# rpilink222.net
KiCad netlist of a schematic drawn in EAGLE
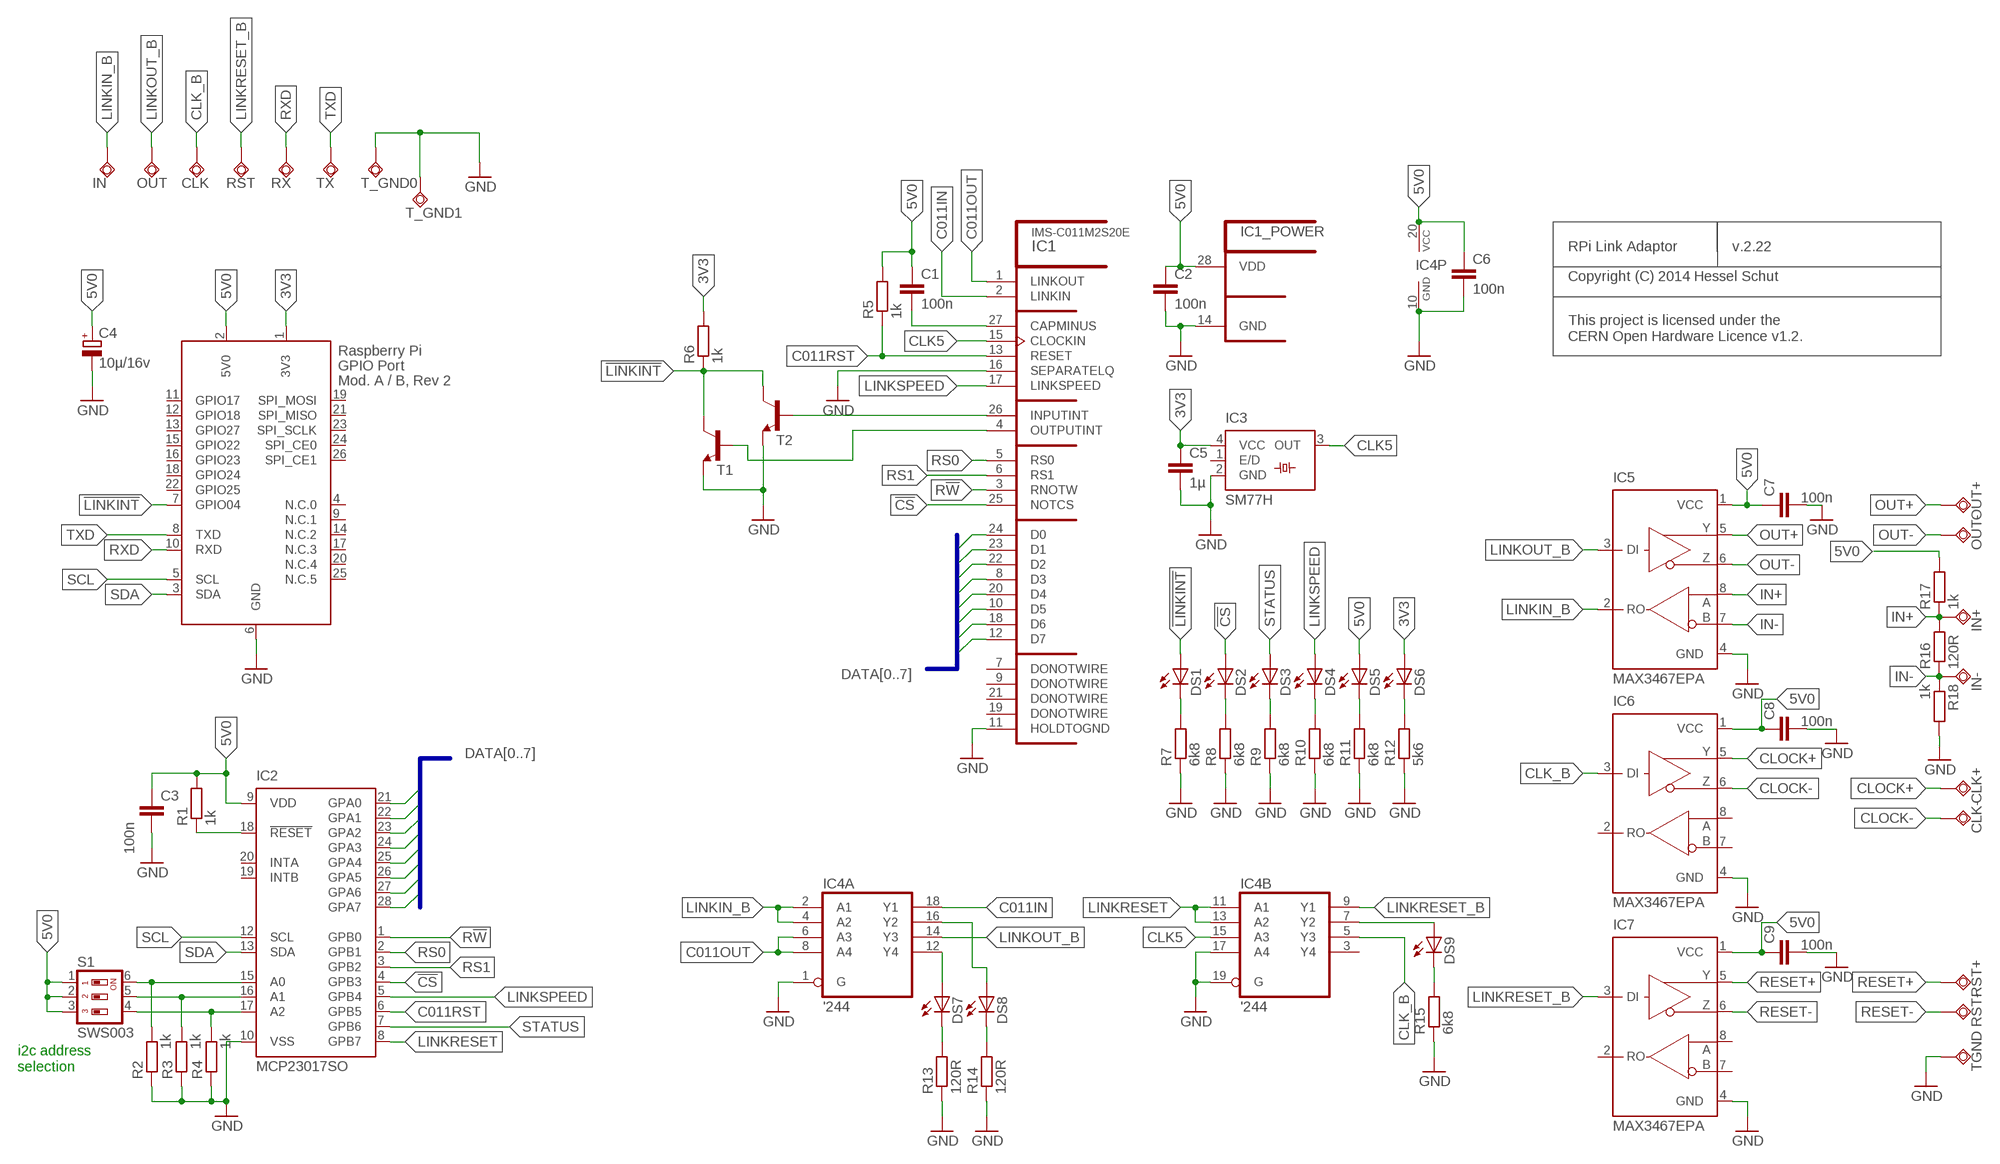
[diagram p0: schematic, sheet 1]

(export (version "E")
  (design (tool "Eeschema 10.0.6"))
  (components
    (comp (ref "C1")
      (value "100n")
      (footprint "eagle-import:C0805")
      (libsource (lib "eagle-import") (part "C-EUC0805"))
    )
    (comp (ref "C2")
      (value "100n")
      (footprint "eagle-import:C0805")
      (libsource (lib "eagle-import") (part "C-EUC0805"))
    )
    (comp (ref "C3")
      (value "100n")
      (footprint "eagle-import:C0805")
      (libsource (lib "eagle-import") (part "C-EUC0805"))
    )
    (comp (ref "C4")
      (value "10µ/16v")
      (footprint "eagle-import:C_6032-28R")
      (libsource (lib "eagle-import") (part "CPOL-EUC/6032-28R"))
    )
    (comp (ref "C5")
      (value "1µ")
      (footprint "eagle-import:C0805")
      (libsource (lib "eagle-import") (part "C-EUC0805"))
    )
    (comp (ref "C6")
      (value "100n")
      (footprint "eagle-import:C0805")
      (libsource (lib "eagle-import") (part "C-EUC0805"))
    )
    (comp (ref "C7")
      (value "100n")
      (footprint "eagle-import:C0805")
      (libsource (lib "eagle-import") (part "C-EUC0805"))
    )
    (comp (ref "C8")
      (value "100n")
      (footprint "eagle-import:C0805")
      (libsource (lib "eagle-import") (part "C-EUC0805"))
    )
    (comp (ref "C9")
      (value "100n")
      (footprint "eagle-import:C0805")
      (libsource (lib "eagle-import") (part "C-EUC0805"))
    )
    (comp (ref "CLK")
      (value "TPSQTP20SQ")
      (footprint "eagle-import:TP20SQ")
      (libsource (lib "eagle-import") (part "TPSQTP20SQ"))
    )
    (comp (ref "CLK+")
      (value "TPSQTP20SQ")
      (footprint "eagle-import:TP20SQ")
      (libsource (lib "eagle-import") (part "TPSQTP20SQ"))
    )
    (comp (ref "CLK-")
      (value "TPSQTP20SQ")
      (footprint "eagle-import:TP20SQ")
      (libsource (lib "eagle-import") (part "TPSQTP20SQ"))
    )
    (comp (ref "DS1")
      (value "LEDCHIP-LED0603")
      (footprint "eagle-import:CHIP-LED0603")
      (libsource (lib "eagle-import") (part "LEDCHIP-LED0603"))
    )
    (comp (ref "DS2")
      (value "LEDCHIP-LED0603")
      (footprint "eagle-import:CHIP-LED0603")
      (libsource (lib "eagle-import") (part "LEDCHIP-LED0603"))
    )
    (comp (ref "DS3")
      (value "LEDCHIP-LED0603")
      (footprint "eagle-import:CHIP-LED0603")
      (libsource (lib "eagle-import") (part "LEDCHIP-LED0603"))
    )
    (comp (ref "DS4")
      (value "LEDCHIP-LED0603")
      (footprint "eagle-import:CHIP-LED0603")
      (libsource (lib "eagle-import") (part "LEDCHIP-LED0603"))
    )
    (comp (ref "DS5")
      (value "LEDCHIP-LED0603")
      (footprint "eagle-import:CHIP-LED0603")
      (libsource (lib "eagle-import") (part "LEDCHIP-LED0603"))
    )
    (comp (ref "DS6")
      (value "LEDCHIP-LED0603")
      (footprint "eagle-import:CHIP-LED0603")
      (libsource (lib "eagle-import") (part "LEDCHIP-LED0603"))
    )
    (comp (ref "DS7")
      (value "LEDCHIP-LED0603")
      (footprint "eagle-import:CHIP-LED0603")
      (libsource (lib "eagle-import") (part "LEDCHIP-LED0603"))
    )
    (comp (ref "DS8")
      (value "LEDCHIP-LED0603")
      (footprint "eagle-import:CHIP-LED0603")
      (libsource (lib "eagle-import") (part "LEDCHIP-LED0603"))
    )
    (comp (ref "DS9")
      (value "LEDCHIP-LED0603")
      (footprint "eagle-import:CHIP-LED0603")
      (libsource (lib "eagle-import") (part "LEDCHIP-LED0603"))
    )
    (comp (ref "IC1")
      (value "IMS-C011M2S20E")
      (footprint "eagle-import:SOJ28-3")
      (libsource (lib "eagle-import") (part "IMS-C011M2ES20"))
    )
    (comp (ref "IC2")
      (value "MCP23017SO")
      (footprint "eagle-import:SO28W")
      (fields (field (name "MF") "MICROCHIP") (field (name "MPN") "MCP23017-E/SO"))
      (libsource (lib "eagle-import") (part "MCP23017SO"))
    )
    (comp (ref "IC3")
      (value "SM77H")
      (footprint "eagle-import:SM77H")
      (libsource (lib "eagle-import") (part "SM77H"))
    )
    (comp (ref "IC4")
      (value "'244")
      (footprint "eagle-import:SO20W")
      (libsource (lib "eagle-import") (part "74244DWAC"))
    )
    (comp (ref "IC5")
      (value "MAX3467EPA")
      (footprint "eagle-import:SO08")
      (libsource (lib "eagle-import") (part "MAX3467PAE"))
    )
    (comp (ref "IC6")
      (value "MAX3467EPA")
      (footprint "eagle-import:SO08")
      (libsource (lib "eagle-import") (part "MAX3467PAE"))
    )
    (comp (ref "IC7")
      (value "MAX3467EPA")
      (footprint "eagle-import:SO08")
      (libsource (lib "eagle-import") (part "MAX3467PAE"))
    )
    (comp (ref "IN")
      (value "TPSQTP20SQ")
      (footprint "eagle-import:TP20SQ")
      (libsource (lib "eagle-import") (part "TPSQTP20SQ"))
    )
    (comp (ref "IN+")
      (value "TPSQTP20SQ")
      (footprint "eagle-import:TP20SQ")
      (libsource (lib "eagle-import") (part "TPSQTP20SQ"))
    )
    (comp (ref "IN-")
      (value "TPSQTP20SQ")
      (footprint "eagle-import:TP20SQ")
      (libsource (lib "eagle-import") (part "TPSQTP20SQ"))
    )
    (comp (ref "OUT")
      (value "TPSQTP20SQ")
      (footprint "eagle-import:TP20SQ")
      (libsource (lib "eagle-import") (part "TPSQTP20SQ"))
    )
    (comp (ref "OUT+")
      (value "TPSQTP20SQ")
      (footprint "eagle-import:TP20SQ")
      (libsource (lib "eagle-import") (part "TPSQTP20SQ"))
    )
    (comp (ref "OUT-")
      (value "TPSQTP20SQ")
      (footprint "eagle-import:TP20SQ")
      (libsource (lib "eagle-import") (part "TPSQTP20SQ"))
    )
    (comp (ref "R1")
      (value "1k")
      (footprint "eagle-import:R0603")
      (libsource (lib "eagle-import") (part "R-EU_R0603"))
    )
    (comp (ref "R2")
      (value "1k")
      (footprint "eagle-import:R0603")
      (libsource (lib "eagle-import") (part "R-EU_R0603"))
    )
    (comp (ref "R3")
      (value "1k")
      (footprint "eagle-import:R0603")
      (libsource (lib "eagle-import") (part "R-EU_R0603"))
    )
    (comp (ref "R4")
      (value "1k")
      (footprint "eagle-import:R0603")
      (libsource (lib "eagle-import") (part "R-EU_R0603"))
    )
    (comp (ref "R5")
      (value "1k")
      (footprint "eagle-import:R0603")
      (libsource (lib "eagle-import") (part "R-EU_R0603"))
    )
    (comp (ref "R6")
      (value "1k")
      (footprint "eagle-import:R0603")
      (libsource (lib "eagle-import") (part "R-EU_R0603"))
    )
    (comp (ref "R7")
      (value "6k8")
      (footprint "eagle-import:R0603")
      (libsource (lib "eagle-import") (part "R-EU_R0603"))
    )
    (comp (ref "R8")
      (value "6k8")
      (footprint "eagle-import:R0603")
      (libsource (lib "eagle-import") (part "R-EU_R0603"))
    )
    (comp (ref "R9")
      (value "6k8")
      (footprint "eagle-import:R0603")
      (libsource (lib "eagle-import") (part "R-EU_R0603"))
    )
    (comp (ref "R10")
      (value "6k8")
      (footprint "eagle-import:R0603")
      (libsource (lib "eagle-import") (part "R-EU_R0603"))
    )
    (comp (ref "R11")
      (value "6k8")
      (footprint "eagle-import:R0603")
      (libsource (lib "eagle-import") (part "R-EU_R0603"))
    )
    (comp (ref "R12")
      (value "5k6")
      (footprint "eagle-import:R0603")
      (libsource (lib "eagle-import") (part "R-EU_R0603"))
    )
    (comp (ref "R13")
      (value "120R")
      (footprint "eagle-import:R0603")
      (libsource (lib "eagle-import") (part "R-EU_R0603"))
    )
    (comp (ref "R14")
      (value "120R")
      (footprint "eagle-import:R0603")
      (libsource (lib "eagle-import") (part "R-EU_R0603"))
    )
    (comp (ref "R15")
      (value "6k8")
      (footprint "eagle-import:R0603")
      (libsource (lib "eagle-import") (part "R-EU_R0603"))
    )
    (comp (ref "R16")
      (value "120R")
      (footprint "eagle-import:R0603")
      (libsource (lib "eagle-import") (part "R-EU_R0603"))
    )
    (comp (ref "R17")
      (value "1k")
      (footprint "eagle-import:R0603")
      (libsource (lib "eagle-import") (part "R-EU_R0603"))
    )
    (comp (ref "R18")
      (value "1k")
      (footprint "eagle-import:R0603")
      (libsource (lib "eagle-import") (part "R-EU_R0603"))
    )
    (comp (ref "RST")
      (value "TPSQTP20SQ")
      (footprint "eagle-import:TP20SQ")
      (libsource (lib "eagle-import") (part "TPSQTP20SQ"))
    )
    (comp (ref "RST+")
      (value "TPSQTP20SQ")
      (footprint "eagle-import:TP20SQ")
      (libsource (lib "eagle-import") (part "TPSQTP20SQ"))
    )
    (comp (ref "RST-")
      (value "TPSQTP20SQ")
      (footprint "eagle-import:TP20SQ")
      (libsource (lib "eagle-import") (part "TPSQTP20SQ"))
    )
    (comp (ref "RX")
      (value "TPSQTP20SQ")
      (footprint "eagle-import:TP20SQ")
      (libsource (lib "eagle-import") (part "TPSQTP20SQ"))
    )
    (comp (ref "S1")
      (value "SWS003")
      (footprint "eagle-import:SMS-003")
      (libsource (lib "eagle-import") (part "SWS003"))
    )
    (comp (ref "T1")
      (value "BC808-NPN-SOT23-BEC")
      (footprint "eagle-import:SOT23-BEC")
      (libsource (lib "eagle-import") (part "-NPN-SOT23-BECBC808"))
    )
    (comp (ref "T2")
      (value "BC808-NPN-SOT23-BEC")
      (footprint "eagle-import:SOT23-BEC")
      (libsource (lib "eagle-import") (part "-NPN-SOT23-BECBC808"))
    )
    (comp (ref "TGND")
      (value "TPSQTP20SQ")
      (footprint "eagle-import:TP20SQ")
      (libsource (lib "eagle-import") (part "TPSQTP20SQ"))
    )
    (comp (ref "TX")
      (value "TPSQTP20SQ")
      (footprint "eagle-import:TP20SQ")
      (libsource (lib "eagle-import") (part "TPSQTP20SQ"))
    )
    (comp (ref "T_GND0")
      (value "TPSQTP20SQ")
      (footprint "eagle-import:TP20SQ")
      (libsource (lib "eagle-import") (part "TPSQTP20SQ"))
    )
    (comp (ref "T_GND1")
      (value "TPSQTP20SQ")
      (footprint "eagle-import:TP20SQ")
      (libsource (lib "eagle-import") (part "TPSQTP20SQ"))
    )
    (comp (ref "X1")
      (value "RASPI_BOARD_AB_E2P")
      (footprint "eagle-import:RASPI_BOARD_AB_EDGES_2DRILL_PAD")
      (libsource (lib "eagle-import") (part "RASPI_BOARD_AB_E2P"))
    )
  )
  (nets
    (net (code "1") (name "/DATA0") (class "Default")
      (node (ref "IC1") (pin "24") (pinfunction "D0_24") (pintype "bidirectional"))
      (node (ref "IC2") (pin "21") (pinfunction "GPA0_21") (pintype "bidirectional"))
    )
    (net (code "2") (name "/DATA1") (class "Default")
      (node (ref "IC1") (pin "23") (pinfunction "D1_23") (pintype "bidirectional"))
      (node (ref "IC2") (pin "22") (pinfunction "GPA1_22") (pintype "bidirectional"))
    )
    (net (code "3") (name "/DATA2") (class "Default")
      (node (ref "IC1") (pin "22") (pinfunction "D2_22") (pintype "bidirectional"))
      (node (ref "IC2") (pin "23") (pinfunction "GPA2_23") (pintype "bidirectional"))
    )
    (net (code "4") (name "/DATA3") (class "Default")
      (node (ref "IC1") (pin "8") (pinfunction "D3_8") (pintype "bidirectional"))
      (node (ref "IC2") (pin "24") (pinfunction "GPA3_24") (pintype "bidirectional"))
    )
    (net (code "5") (name "/DATA4") (class "Default")
      (node (ref "IC1") (pin "20") (pinfunction "D4_20") (pintype "bidirectional"))
      (node (ref "IC2") (pin "25") (pinfunction "GPA4_25") (pintype "bidirectional"))
    )
    (net (code "6") (name "/DATA5") (class "Default")
      (node (ref "IC1") (pin "10") (pinfunction "D5_10") (pintype "bidirectional"))
      (node (ref "IC2") (pin "26") (pinfunction "GPA5_26") (pintype "bidirectional"))
    )
    (net (code "7") (name "/DATA6") (class "Default")
      (node (ref "IC1") (pin "18") (pinfunction "D6_18") (pintype "bidirectional"))
      (node (ref "IC2") (pin "27") (pinfunction "GPA6_27") (pintype "bidirectional"))
    )
    (net (code "8") (name "/DATA7") (class "Default")
      (node (ref "IC1") (pin "12") (pinfunction "D7_12") (pintype "bidirectional"))
      (node (ref "IC2") (pin "28") (pinfunction "GPA7_28") (pintype "bidirectional"))
    )
    (net (code "10") (name "/R~{W}") (class "Default")
      (node (ref "IC1") (pin "3") (pinfunction "RNOTW_3") (pintype "input"))
      (node (ref "IC2") (pin "1") (pinfunction "GPB0_1") (pintype "bidirectional"))
    )
    (net (code "11") (name "/~{CS}") (class "Default")
      (node (ref "DS2") (pin "A") (pinfunction "A_A") (pintype "passive"))
      (node (ref "IC1") (pin "25") (pinfunction "NOTCS_25") (pintype "input"))
      (node (ref "IC2") (pin "4") (pinfunction "GPB3_4") (pintype "bidirectional"))
    )
    (net (code "12") (name "/~{LINKINT}") (class "Default")
      (node (ref "DS1") (pin "A") (pinfunction "A_A") (pintype "passive"))
      (node (ref "R6") (pin "1") (pinfunction "1_1") (pintype "passive"))
      (node (ref "T1") (pin "C") (pinfunction "C_C") (pintype "passive"))
      (node (ref "T2") (pin "C") (pinfunction "C_C") (pintype "passive"))
      (node (ref "X1") (pin "7") (pinfunction "GPIO04_7") (pintype "bidirectional"))
    )
    (net (code "13") (name "3V3") (class "Default")
      (node (ref "C5") (pin "1") (pinfunction "1_1") (pintype "passive"))
      (node (ref "DS6") (pin "A") (pinfunction "A_A") (pintype "passive"))
      (node (ref "IC3") (pin "4") (pinfunction "VCC_4") (pintype "power_in"))
      (node (ref "R6") (pin "2") (pinfunction "2_2") (pintype "passive"))
      (node (ref "X1") (pin "1") (pinfunction "3V3_1") (pintype "power_in"))
    )
    (net (code "14") (name "5V0") (class "Default")
      (node (ref "C1") (pin "1") (pinfunction "1_1") (pintype "passive"))
      (node (ref "C2") (pin "1") (pinfunction "1_1") (pintype "passive"))
      (node (ref "C3") (pin "1") (pinfunction "1_1") (pintype "passive"))
      (node (ref "C4") (pin "+") (pinfunction "+_+") (pintype "passive"))
      (node (ref "C6") (pin "1") (pinfunction "1_1") (pintype "passive"))
      (node (ref "C7") (pin "1") (pinfunction "1_1") (pintype "passive"))
      (node (ref "C8") (pin "1") (pinfunction "1_1") (pintype "passive"))
      (node (ref "C9") (pin "1") (pinfunction "1_1") (pintype "passive"))
      (node (ref "DS5") (pin "A") (pinfunction "A_A") (pintype "passive"))
      (node (ref "IC1") (pin "28") (pinfunction "VDD_28") (pintype "power_in"))
      (node (ref "IC2") (pin "9") (pinfunction "VDD_9") (pintype "power_in"))
      (node (ref "IC4") (pin "20") (pinfunction "VCC_20") (pintype "power_in"))
      (node (ref "IC5") (pin "1") (pinfunction "VCC_1") (pintype "power_in"))
      (node (ref "IC6") (pin "1") (pinfunction "VCC_1") (pintype "power_in"))
      (node (ref "IC7") (pin "1") (pinfunction "VCC_1") (pintype "power_in"))
      (node (ref "R1") (pin "2") (pinfunction "2_2") (pintype "passive"))
      (node (ref "R17") (pin "2") (pinfunction "2_2") (pintype "passive"))
      (node (ref "R5") (pin "2") (pinfunction "2_2") (pintype "passive"))
      (node (ref "S1") (pin "1") (pinfunction "1_1") (pintype "passive"))
      (node (ref "S1") (pin "2") (pinfunction "2_2") (pintype "passive"))
      (node (ref "S1") (pin "3") (pinfunction "3_3") (pintype "passive"))
      (node (ref "X1") (pin "2") (pinfunction "5V0_2") (pintype "power_in"))
    )
    (net (code "15") (name "C011IN") (class "Default")
      (node (ref "IC1") (pin "2") (pinfunction "LINKIN_2") (pintype "input"))
      (node (ref "IC4") (pin "18") (pinfunction "Y1_18") (pintype "tri_state"))
    )
    (net (code "16") (name "C011OUT") (class "Default")
      (node (ref "IC1") (pin "1") (pinfunction "LINKOUT_1") (pintype "output"))
      (node (ref "IC4") (pin "6") (pinfunction "A3_6") (pintype "input"))
      (node (ref "IC4") (pin "8") (pinfunction "A4_8") (pintype "input"))
    )
    (net (code "17") (name "C011RST") (class "Default")
      (node (ref "IC1") (pin "13") (pinfunction "RESET_13") (pintype "input"))
      (node (ref "IC2") (pin "6") (pinfunction "GPB5_6") (pintype "bidirectional"))
      (node (ref "R5") (pin "1") (pinfunction "1_1") (pintype "passive"))
    )
    (net (code "18") (name "CLK5") (class "Default")
      (node (ref "IC1") (pin "15") (pinfunction "CLOCKIN_15") (pintype "input"))
      (node (ref "IC3") (pin "3") (pinfunction "OUT_3") (pintype "output"))
      (node (ref "IC4") (pin "15") (pinfunction "A3_15") (pintype "input"))
    )
    (net (code "19") (name "CLK_B") (class "Default")
      (node (ref "CLK") (pin "TP") (pinfunction "TP_TP") (pintype "input"))
      (node (ref "IC4") (pin "5") (pinfunction "Y3_5") (pintype "tri_state"))
      (node (ref "IC6") (pin "3") (pinfunction "DI_3") (pintype "input"))
    )
    (net (code "20") (name "CLOCK+") (class "Default")
      (node (ref "CLK+") (pin "TP") (pinfunction "TP_TP") (pintype "input"))
      (node (ref "IC6") (pin "5") (pinfunction "Y_5") (pintype "passive"))
    )
    (net (code "21") (name "CLOCK-") (class "Default")
      (node (ref "CLK-") (pin "TP") (pinfunction "TP_TP") (pintype "input"))
      (node (ref "IC6") (pin "6") (pinfunction "Z_6") (pintype "passive"))
    )
    (net (code "22") (name "GND") (class "Default")
      (node (ref "C2") (pin "2") (pinfunction "2_2") (pintype "passive"))
      (node (ref "C3") (pin "2") (pinfunction "2_2") (pintype "passive"))
      (node (ref "C4") (pin "-") (pinfunction "-_-") (pintype "passive"))
      (node (ref "C5") (pin "2") (pinfunction "2_2") (pintype "passive"))
      (node (ref "C6") (pin "2") (pinfunction "2_2") (pintype "passive"))
      (node (ref "C7") (pin "2") (pinfunction "2_2") (pintype "passive"))
      (node (ref "C8") (pin "2") (pinfunction "2_2") (pintype "passive"))
      (node (ref "C9") (pin "2") (pinfunction "2_2") (pintype "passive"))
      (node (ref "IC1") (pin "11") (pinfunction "HOLDTOGND_11") (pintype "passive"))
      (node (ref "IC1") (pin "14") (pinfunction "GND_14") (pintype "power_in"))
      (node (ref "IC1") (pin "16") (pinfunction "SEPARATELQ_16") (pintype "input"))
      (node (ref "IC2") (pin "10") (pinfunction "VSS_10") (pintype "power_in"))
      (node (ref "IC3") (pin "2") (pinfunction "GND_2") (pintype "power_in"))
      (node (ref "IC4") (pin "1") (pinfunction "G_1") (pintype "input"))
      (node (ref "IC4") (pin "10") (pinfunction "GND_10") (pintype "power_in"))
      (node (ref "IC4") (pin "17") (pinfunction "A4_17") (pintype "input"))
      (node (ref "IC4") (pin "19") (pinfunction "G_19") (pintype "input"))
      (node (ref "IC5") (pin "4") (pinfunction "GND_4") (pintype "power_in"))
      (node (ref "IC6") (pin "4") (pinfunction "GND_4") (pintype "power_in"))
      (node (ref "IC7") (pin "4") (pinfunction "GND_4") (pintype "power_in"))
      (node (ref "R10") (pin "1") (pinfunction "1_1") (pintype "passive"))
      (node (ref "R11") (pin "1") (pinfunction "1_1") (pintype "passive"))
      (node (ref "R12") (pin "1") (pinfunction "1_1") (pintype "passive"))
      (node (ref "R13") (pin "1") (pinfunction "1_1") (pintype "passive"))
      (node (ref "R14") (pin "1") (pinfunction "1_1") (pintype "passive"))
      (node (ref "R15") (pin "1") (pinfunction "1_1") (pintype "passive"))
      (node (ref "R18") (pin "2") (pinfunction "2_2") (pintype "passive"))
      (node (ref "R2") (pin "1") (pinfunction "1_1") (pintype "passive"))
      (node (ref "R3") (pin "1") (pinfunction "1_1") (pintype "passive"))
      (node (ref "R4") (pin "1") (pinfunction "1_1") (pintype "passive"))
      (node (ref "R7") (pin "1") (pinfunction "1_1") (pintype "passive"))
      (node (ref "R8") (pin "1") (pinfunction "1_1") (pintype "passive"))
      (node (ref "R9") (pin "1") (pinfunction "1_1") (pintype "passive"))
      (node (ref "T1") (pin "E") (pinfunction "E_E") (pintype "passive"))
      (node (ref "T2") (pin "E") (pinfunction "E_E") (pintype "passive"))
      (node (ref "TGND") (pin "TP") (pinfunction "TP_TP") (pintype "input"))
      (node (ref "T_GND0") (pin "TP") (pinfunction "TP_TP") (pintype "input"))
      (node (ref "T_GND1") (pin "TP") (pinfunction "TP_TP") (pintype "input"))
      (node (ref "X1") (pin "6") (pinfunction "GND_6") (pintype "power_in"))
    )
    (net (code "23") (name "IN+") (class "Default")
      (node (ref "IC5") (pin "8") (pinfunction "A_8") (pintype "passive"))
      (node (ref "IN+") (pin "TP") (pinfunction "TP_TP") (pintype "input"))
      (node (ref "R16") (pin "2") (pinfunction "2_2") (pintype "passive"))
      (node (ref "R17") (pin "1") (pinfunction "1_1") (pintype "passive"))
    )
    (net (code "24") (name "IN-") (class "Default")
      (node (ref "IC5") (pin "7") (pinfunction "B_7") (pintype "passive"))
      (node (ref "IN-") (pin "TP") (pinfunction "TP_TP") (pintype "input"))
      (node (ref "R16") (pin "1") (pinfunction "1_1") (pintype "passive"))
      (node (ref "R18") (pin "1") (pinfunction "1_1") (pintype "passive"))
    )
    (net (code "25") (name "LINKIN_B") (class "Default")
      (node (ref "IC4") (pin "2") (pinfunction "A1_2") (pintype "input"))
      (node (ref "IC4") (pin "4") (pinfunction "A2_4") (pintype "input"))
      (node (ref "IC5") (pin "2") (pinfunction "RO_2") (pintype "output"))
      (node (ref "IN") (pin "TP") (pinfunction "TP_TP") (pintype "input"))
    )
    (net (code "26") (name "LINKOUT_B") (class "Default")
      (node (ref "IC4") (pin "14") (pinfunction "Y3_14") (pintype "tri_state"))
      (node (ref "IC5") (pin "3") (pinfunction "DI_3") (pintype "input"))
      (node (ref "OUT") (pin "TP") (pinfunction "TP_TP") (pintype "input"))
    )
    (net (code "27") (name "LINKRESET") (class "Default")
      (node (ref "IC2") (pin "8") (pinfunction "GPB7_8") (pintype "bidirectional"))
      (node (ref "IC4") (pin "11") (pinfunction "A1_11") (pintype "input"))
      (node (ref "IC4") (pin "13") (pinfunction "A2_13") (pintype "input"))
    )
    (net (code "28") (name "LINKRESET_B") (class "Default")
      (node (ref "IC4") (pin "9") (pinfunction "Y1_9") (pintype "tri_state"))
      (node (ref "IC7") (pin "3") (pinfunction "DI_3") (pintype "input"))
      (node (ref "RST") (pin "TP") (pinfunction "TP_TP") (pintype "input"))
    )
    (net (code "29") (name "LINKSPEED") (class "Default")
      (node (ref "DS4") (pin "A") (pinfunction "A_A") (pintype "passive"))
      (node (ref "IC1") (pin "17") (pinfunction "LINKSPEED_17") (pintype "input"))
      (node (ref "IC2") (pin "5") (pinfunction "GPB4_5") (pintype "bidirectional"))
    )
    (net (code "30") (name "Net-(DS1-PadC)") (class "Default")
      (node (ref "DS1") (pin "C") (pinfunction "C_C") (pintype "passive"))
      (node (ref "R7") (pin "2") (pinfunction "2_2") (pintype "passive"))
    )
    (net (code "31") (name "Net-(DS2-PadC)") (class "Default")
      (node (ref "DS2") (pin "C") (pinfunction "C_C") (pintype "passive"))
      (node (ref "R8") (pin "2") (pinfunction "2_2") (pintype "passive"))
    )
    (net (code "32") (name "Net-(DS3-PadC)") (class "Default")
      (node (ref "DS3") (pin "C") (pinfunction "C_C") (pintype "passive"))
      (node (ref "R9") (pin "2") (pinfunction "2_2") (pintype "passive"))
    )
    (net (code "33") (name "Net-(DS4-PadC)") (class "Default")
      (node (ref "DS4") (pin "C") (pinfunction "C_C") (pintype "passive"))
      (node (ref "R10") (pin "2") (pinfunction "2_2") (pintype "passive"))
    )
    (net (code "34") (name "Net-(DS5-PadC)") (class "Default")
      (node (ref "DS5") (pin "C") (pinfunction "C_C") (pintype "passive"))
      (node (ref "R11") (pin "2") (pinfunction "2_2") (pintype "passive"))
    )
    (net (code "35") (name "Net-(DS6-PadC)") (class "Default")
      (node (ref "DS6") (pin "C") (pinfunction "C_C") (pintype "passive"))
      (node (ref "R12") (pin "2") (pinfunction "2_2") (pintype "passive"))
    )
    (net (code "36") (name "Net-(DS7-PadC)") (class "Default")
      (node (ref "DS7") (pin "C") (pinfunction "C_C") (pintype "passive"))
      (node (ref "R13") (pin "2") (pinfunction "2_2") (pintype "passive"))
    )
    (net (code "37") (name "Net-(DS8-PadC)") (class "Default")
      (node (ref "DS8") (pin "C") (pinfunction "C_C") (pintype "passive"))
      (node (ref "R14") (pin "2") (pinfunction "2_2") (pintype "passive"))
    )
    (net (code "38") (name "Net-(DS9-PadC)") (class "Default")
      (node (ref "DS9") (pin "C") (pinfunction "C_C") (pintype "passive"))
      (node (ref "R15") (pin "2") (pinfunction "2_2") (pintype "passive"))
    )
    (net (code "39") (name "Net-(IC1A-CAPMINUS)") (class "Default")
      (node (ref "C1") (pin "2") (pinfunction "2_2") (pintype "passive"))
      (node (ref "IC1") (pin "27") (pinfunction "CAPMINUS_27") (pintype "passive"))
    )
    (net (code "40") (name "Net-(IC1A-INPUTINT)") (class "Default")
      (node (ref "IC1") (pin "26") (pinfunction "INPUTINT_26") (pintype "output"))
      (node (ref "T2") (pin "B") (pinfunction "B_B") (pintype "passive"))
    )
    (net (code "41") (name "Net-(IC1A-OUTPUTINT)") (class "Default")
      (node (ref "IC1") (pin "4") (pinfunction "OUTPUTINT_4") (pintype "output"))
      (node (ref "T1") (pin "B") (pinfunction "B_B") (pintype "passive"))
    )
    (net (code "42") (name "Net-(IC2-A0)") (class "Default")
      (node (ref "IC2") (pin "15") (pinfunction "A0_15") (pintype "input"))
      (node (ref "R2") (pin "2") (pinfunction "2_2") (pintype "passive"))
      (node (ref "S1") (pin "6") (pinfunction "6_6") (pintype "passive"))
    )
    (net (code "43") (name "Net-(IC2-A1)") (class "Default")
      (node (ref "IC2") (pin "16") (pinfunction "A1_16") (pintype "input"))
      (node (ref "R3") (pin "2") (pinfunction "2_2") (pintype "passive"))
      (node (ref "S1") (pin "5") (pinfunction "5_5") (pintype "passive"))
    )
    (net (code "44") (name "Net-(IC2-A2)") (class "Default")
      (node (ref "IC2") (pin "17") (pinfunction "A2_17") (pintype "input"))
      (node (ref "R4") (pin "2") (pinfunction "2_2") (pintype "passive"))
      (node (ref "S1") (pin "4") (pinfunction "4_4") (pintype "passive"))
    )
    (net (code "45") (name "Net-(IC2-~{RESET})") (class "Default")
      (node (ref "IC2") (pin "18") (pinfunction "~{RESET}_18") (pintype "input"))
      (node (ref "R1") (pin "1") (pinfunction "1_1") (pintype "passive"))
    )
    (net (code "46") (name "Net-(IC4A-Y2)") (class "Default")
      (node (ref "DS8") (pin "A") (pinfunction "A_A") (pintype "passive"))
      (node (ref "IC4") (pin "16") (pinfunction "Y2_16") (pintype "tri_state"))
    )
    (net (code "47") (name "Net-(IC4A-Y4)") (class "Default")
      (node (ref "DS7") (pin "A") (pinfunction "A_A") (pintype "passive"))
      (node (ref "IC4") (pin "12") (pinfunction "Y4_12") (pintype "tri_state"))
    )
    (net (code "48") (name "Net-(IC4B-Y2)") (class "Default")
      (node (ref "DS9") (pin "A") (pinfunction "A_A") (pintype "passive"))
      (node (ref "IC4") (pin "7") (pinfunction "Y2_7") (pintype "tri_state"))
    )
    (net (code "49") (name "OUT+") (class "Default")
      (node (ref "IC5") (pin "5") (pinfunction "Y_5") (pintype "passive"))
      (node (ref "OUT+") (pin "TP") (pinfunction "TP_TP") (pintype "input"))
    )
    (net (code "50") (name "OUT-") (class "Default")
      (node (ref "IC5") (pin "6") (pinfunction "Z_6") (pintype "passive"))
      (node (ref "OUT-") (pin "TP") (pinfunction "TP_TP") (pintype "input"))
    )
    (net (code "51") (name "RESET+") (class "Default")
      (node (ref "IC7") (pin "5") (pinfunction "Y_5") (pintype "passive"))
      (node (ref "RST+") (pin "TP") (pinfunction "TP_TP") (pintype "input"))
    )
    (net (code "52") (name "RESET-") (class "Default")
      (node (ref "IC7") (pin "6") (pinfunction "Z_6") (pintype "passive"))
      (node (ref "RST-") (pin "TP") (pinfunction "TP_TP") (pintype "input"))
    )
    (net (code "53") (name "RS0") (class "Default")
      (node (ref "IC1") (pin "5") (pinfunction "RS0_5") (pintype "input"))
      (node (ref "IC2") (pin "2") (pinfunction "GPB1_2") (pintype "bidirectional"))
    )
    (net (code "54") (name "RS1") (class "Default")
      (node (ref "IC1") (pin "6") (pinfunction "RS1_6") (pintype "input"))
      (node (ref "IC2") (pin "3") (pinfunction "GPB2_3") (pintype "bidirectional"))
    )
    (net (code "55") (name "RXD") (class "Default")
      (node (ref "RX") (pin "TP") (pinfunction "TP_TP") (pintype "input"))
      (node (ref "X1") (pin "10") (pinfunction "RXD_10") (pintype "bidirectional"))
    )
    (net (code "56") (name "SCL") (class "Default")
      (node (ref "IC2") (pin "12") (pinfunction "SCL_12") (pintype "input"))
      (node (ref "X1") (pin "5") (pinfunction "SCL_5") (pintype "bidirectional"))
    )
    (net (code "57") (name "SDA") (class "Default")
      (node (ref "IC2") (pin "13") (pinfunction "SDA_13") (pintype "bidirectional"))
      (node (ref "X1") (pin "3") (pinfunction "SDA_3") (pintype "bidirectional"))
    )
    (net (code "58") (name "STATUS") (class "Default")
      (node (ref "DS3") (pin "A") (pinfunction "A_A") (pintype "passive"))
      (node (ref "IC2") (pin "7") (pinfunction "GPB6_7") (pintype "bidirectional"))
    )
    (net (code "59") (name "TXD") (class "Default")
      (node (ref "TX") (pin "TP") (pinfunction "TP_TP") (pintype "input"))
      (node (ref "X1") (pin "8") (pinfunction "TXD_8") (pintype "bidirectional"))
    )
    (net (code "60") (name "unconnected-(IC1A-DONOTWIRE-Pad7)") (class "Default")
      (node (ref "IC1") (pin "7") (pinfunction "DONOTWIRE_7") (pintype "no_connect"))
    )
    (net (code "61") (name "unconnected-(IC1A-DONOTWIRE-Pad9)") (class "Default")
      (node (ref "IC1") (pin "9") (pinfunction "DONOTWIRE_9") (pintype "no_connect"))
    )
    (net (code "62") (name "unconnected-(IC1A-DONOTWIRE-Pad19)") (class "Default")
      (node (ref "IC1") (pin "19") (pinfunction "DONOTWIRE_19") (pintype "no_connect"))
    )
    (net (code "63") (name "unconnected-(IC1A-DONOTWIRE-Pad21)") (class "Default")
      (node (ref "IC1") (pin "21") (pinfunction "DONOTWIRE_21") (pintype "no_connect"))
    )
    (net (code "64") (name "unconnected-(IC2-INTA-Pad20)") (class "Default")
      (node (ref "IC2") (pin "20") (pinfunction "INTA_20") (pintype "output"))
    )
    (net (code "65") (name "unconnected-(IC2-INTB-Pad19)") (class "Default")
      (node (ref "IC2") (pin "19") (pinfunction "INTB_19") (pintype "output"))
    )
    (net (code "66") (name "unconnected-(IC3-E{slash}D-Pad1)") (class "Default")
      (node (ref "IC3") (pin "1") (pinfunction "E/D_1") (pintype "input"))
    )
    (net (code "67") (name "unconnected-(IC4B-Y4-Pad3)") (class "Default")
      (node (ref "IC4") (pin "3") (pinfunction "Y4_3") (pintype "tri_state"))
    )
    (net (code "68") (name "unconnected-(IC6-A-Pad8)") (class "Default")
      (node (ref "IC6") (pin "8") (pinfunction "A_8") (pintype "passive"))
    )
    (net (code "69") (name "unconnected-(IC6-B-Pad7)") (class "Default")
      (node (ref "IC6") (pin "7") (pinfunction "B_7") (pintype "passive"))
    )
    (net (code "70") (name "unconnected-(IC6-RO-Pad2)") (class "Default")
      (node (ref "IC6") (pin "2") (pinfunction "RO_2") (pintype "output"))
    )
    (net (code "71") (name "unconnected-(IC7-A-Pad8)") (class "Default")
      (node (ref "IC7") (pin "8") (pinfunction "A_8") (pintype "passive"))
    )
    (net (code "72") (name "unconnected-(IC7-B-Pad7)") (class "Default")
      (node (ref "IC7") (pin "7") (pinfunction "B_7") (pintype "passive"))
    )
    (net (code "73") (name "unconnected-(IC7-RO-Pad2)") (class "Default")
      (node (ref "IC7") (pin "2") (pinfunction "RO_2") (pintype "output"))
    )
    (net (code "74") (name "unconnected-(X1-GPIO17-Pad11)") (class "Default")
      (node (ref "X1") (pin "11") (pinfunction "GPIO17_11") (pintype "bidirectional"))
    )
    (net (code "75") (name "unconnected-(X1-GPIO18-Pad12)") (class "Default")
      (node (ref "X1") (pin "12") (pinfunction "GPIO18_12") (pintype "bidirectional"))
    )
    (net (code "76") (name "unconnected-(X1-GPIO22-Pad15)") (class "Default")
      (node (ref "X1") (pin "15") (pinfunction "GPIO22_15") (pintype "bidirectional"))
    )
    (net (code "77") (name "unconnected-(X1-GPIO23-Pad16)") (class "Default")
      (node (ref "X1") (pin "16") (pinfunction "GPIO23_16") (pintype "bidirectional"))
    )
    (net (code "78") (name "unconnected-(X1-GPIO24-Pad18)") (class "Default")
      (node (ref "X1") (pin "18") (pinfunction "GPIO24_18") (pintype "bidirectional"))
    )
    (net (code "79") (name "unconnected-(X1-GPIO25-Pad22)") (class "Default")
      (node (ref "X1") (pin "22") (pinfunction "GPIO25_22") (pintype "bidirectional"))
    )
    (net (code "80") (name "unconnected-(X1-GPIO27-Pad13)") (class "Default")
      (node (ref "X1") (pin "13") (pinfunction "GPIO27_13") (pintype "bidirectional"))
    )
    (net (code "81") (name "unconnected-(X1-N.C.0-Pad4)") (class "Default")
      (node (ref "X1") (pin "4") (pinfunction "N.C.0_4") (pintype "no_connect"))
    )
    (net (code "82") (name "unconnected-(X1-N.C.1-Pad9)") (class "Default")
      (node (ref "X1") (pin "9") (pinfunction "N.C.1_9") (pintype "no_connect"))
    )
    (net (code "83") (name "unconnected-(X1-N.C.2-Pad14)") (class "Default")
      (node (ref "X1") (pin "14") (pinfunction "N.C.2_14") (pintype "no_connect"))
    )
    (net (code "84") (name "unconnected-(X1-N.C.3-Pad17)") (class "Default")
      (node (ref "X1") (pin "17") (pinfunction "N.C.3_17") (pintype "no_connect"))
    )
    (net (code "85") (name "unconnected-(X1-N.C.4-Pad20)") (class "Default")
      (node (ref "X1") (pin "20") (pinfunction "N.C.4_20") (pintype "no_connect"))
    )
    (net (code "86") (name "unconnected-(X1-N.C.5-Pad25)") (class "Default")
      (node (ref "X1") (pin "25") (pinfunction "N.C.5_25") (pintype "no_connect"))
    )
    (net (code "87") (name "unconnected-(X1-SPI_CE0-Pad24)") (class "Default")
      (node (ref "X1") (pin "24") (pinfunction "SPI_CE0_24") (pintype "bidirectional"))
    )
    (net (code "88") (name "unconnected-(X1-SPI_CE1-Pad26)") (class "Default")
      (node (ref "X1") (pin "26") (pinfunction "SPI_CE1_26") (pintype "bidirectional"))
    )
    (net (code "89") (name "unconnected-(X1-SPI_MISO-Pad21)") (class "Default")
      (node (ref "X1") (pin "21") (pinfunction "SPI_MISO_21") (pintype "bidirectional"))
    )
    (net (code "90") (name "unconnected-(X1-SPI_MOSI-Pad19)") (class "Default")
      (node (ref "X1") (pin "19") (pinfunction "SPI_MOSI_19") (pintype "bidirectional"))
    )
    (net (code "91") (name "unconnected-(X1-SPI_SCLK-Pad23)") (class "Default")
      (node (ref "X1") (pin "23") (pinfunction "SPI_SCLK_23") (pintype "bidirectional"))
    )
  )
)
